# TinyISD1700_V2_2014-08-29sop.net
KiCad netlist of a schematic drawn in EAGLE
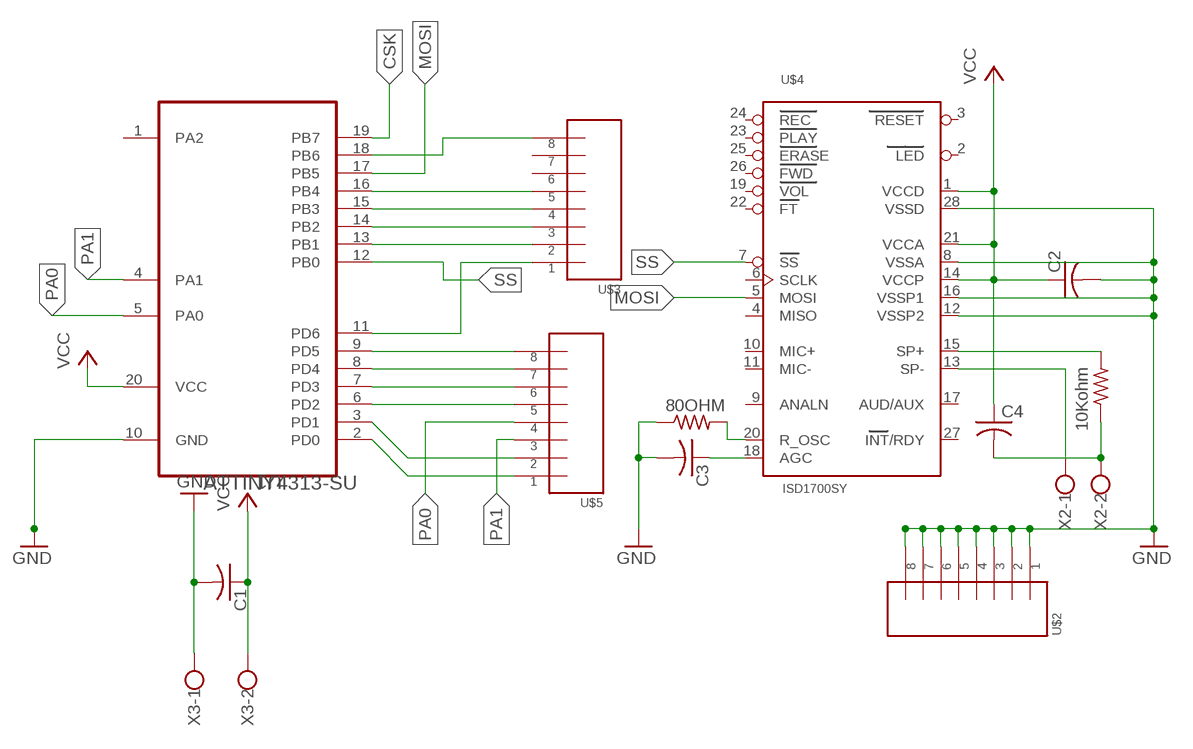
[diagram p0: schematic, sheet 1]

(export (version "E")
  (design (tool "Eeschema 10.0.6"))
  (components
    (comp (ref "80OHM")
      (value "R-US_0204/2V")
      (footprint "eagle-import:0204V")
      (libsource (lib "eagle-import") (part "R-US_0204/2V"))
    )
    (comp (ref "80OHM1")
      (value "10Kohm")
      (footprint "eagle-import:0204V")
      (libsource (lib "eagle-import") (part "R-US_0204/2V"))
    )
    (comp (ref "C1")
      (value "C-US050-030X075")
      (footprint "eagle-import:C050-030X075")
      (libsource (lib "eagle-import") (part "C-US050-030X075"))
    )
    (comp (ref "C2")
      (value "C-US050-030X075")
      (footprint "eagle-import:C050-030X075")
      (libsource (lib "eagle-import") (part "C-US050-030X075"))
    )
    (comp (ref "C3")
      (value "C-US050-030X075")
      (footprint "eagle-import:C050-030X075")
      (libsource (lib "eagle-import") (part "C-US050-030X075"))
    )
    (comp (ref "C4")
      (value "C-US050-030X075")
      (footprint "eagle-import:C050-030X075")
      (libsource (lib "eagle-import") (part "C-US050-030X075"))
    )
    (comp (ref "U$2")
      (value "8PIN_HEADER")
      (footprint "eagle-import:8PIN_HEADER")
      (fields (field (name "MF") "RENESAS") (field (name "MPN") "YSDKS128E10"))
      (libsource (lib "eagle-import") (part "8PIN_HEADER"))
    )
    (comp (ref "U$3")
      (value "8PIN_HEADER")
      (footprint "eagle-import:8PIN_HEADER")
      (fields (field (name "MF") "RENESAS") (field (name "MPN") "YSDKS128E10"))
      (libsource (lib "eagle-import") (part "8PIN_HEADER"))
    )
    (comp (ref "U$4")
      (value "ISD1700SY")
      (footprint "eagle-import:SO28W")
      (libsource (lib "eagle-import") (part "ISD1700SY"))
    )
    (comp (ref "U$5")
      (value "8PIN_HEADER")
      (footprint "eagle-import:8PIN_HEADER")
      (fields (field (name "MF") "RENESAS") (field (name "MPN") "YSDKS128E10"))
      (libsource (lib "eagle-import") (part "8PIN_HEADER"))
    )
    (comp (ref "U1")
      (value "ATTINY4313-SU")
      (footprint "eagle-import:SOIC127P1032X265-20N")
      (fields (field (name "MF") "MICROCHIP"))
      (libsource (lib "eagle-import") (part "ATTINY4313-SU"))
    )
    (comp (ref "X2")
      (value "W237-102")
      (footprint "eagle-import:W237-102")
      (fields (field (name "MPN") "237-102"))
      (libsource (lib "eagle-import") (part "W237-102"))
    )
    (comp (ref "X3")
      (value "W237-102")
      (footprint "eagle-import:W237-102")
      (fields (field (name "MPN") "237-102") (field (name "OC_NEWARK") "70K9898"))
      (libsource (lib "eagle-import") (part "W237-102"))
    )
  )
  (nets
    (net (code "1") (name "CSK") (class "Default")
      (node (ref "U1") (pin "19") (pinfunction "PB7_19") (pintype "bidirectional"))
    )
    (net (code "2") (name "GND") (class "Default")
      (node (ref "80OHM") (pin "1") (pinfunction "1_1") (pintype "passive"))
      (node (ref "C1") (pin "2") (pinfunction "2_2") (pintype "passive"))
      (node (ref "C2") (pin "2") (pinfunction "2_2") (pintype "passive"))
      (node (ref "C3") (pin "2") (pinfunction "2_2") (pintype "passive"))
      (node (ref "U$2") (pin "P$1") (pinfunction "P$1_P$1") (pintype "bidirectional"))
      (node (ref "U$2") (pin "P$2") (pinfunction "P$2_P$2") (pintype "bidirectional"))
      (node (ref "U$2") (pin "P$3") (pinfunction "P$3_P$3") (pintype "bidirectional"))
      (node (ref "U$2") (pin "P$4") (pinfunction "P$4_P$4") (pintype "bidirectional"))
      (node (ref "U$2") (pin "P$5") (pinfunction "P$5_P$5") (pintype "bidirectional"))
      (node (ref "U$2") (pin "P$6") (pinfunction "P$6_P$6") (pintype "bidirectional"))
      (node (ref "U$2") (pin "P$7") (pinfunction "P$7_P$7") (pintype "bidirectional"))
      (node (ref "U$2") (pin "P$8") (pinfunction "P$8_P$8") (pintype "bidirectional"))
      (node (ref "U$4") (pin "12") (pinfunction "VSSP2_12") (pintype "power_in"))
      (node (ref "U$4") (pin "16") (pinfunction "VSSP1_16") (pintype "power_in"))
      (node (ref "U$4") (pin "28") (pinfunction "VSSD_28") (pintype "power_in"))
      (node (ref "U$4") (pin "8") (pinfunction "VSSA_8") (pintype "power_in"))
      (node (ref "U1") (pin "10") (pinfunction "GND_10") (pintype "passive"))
      (node (ref "X3") (pin "1") (pinfunction "KL_1") (pintype "passive"))
    )
    (net (code "3") (name "MOSI") (class "Default")
      (node (ref "U$4") (pin "5") (pinfunction "MOSI_5") (pintype "input"))
      (node (ref "U1") (pin "17") (pinfunction "PB5_17") (pintype "bidirectional"))
    )
    (net (code "4") (name "Net-(U$4-AGC)") (class "Default")
      (node (ref "C3") (pin "1") (pinfunction "1_1") (pintype "passive"))
      (node (ref "U$4") (pin "18") (pinfunction "AGC_18") (pintype "passive"))
    )
    (net (code "5") (name "Net-(U$4-R_OSC)") (class "Default")
      (node (ref "80OHM") (pin "2") (pinfunction "2_2") (pintype "passive"))
      (node (ref "U$4") (pin "20") (pinfunction "R_OSC_20") (pintype "passive"))
    )
    (net (code "6") (name "Net-(U$4-SP+)") (class "Default")
      (node (ref "80OHM1") (pin "2") (pinfunction "2_2") (pintype "passive"))
      (node (ref "U$4") (pin "15") (pinfunction "SP+_15") (pintype "output"))
    )
    (net (code "7") (name "Net-(U$4-SP-)") (class "Default")
      (node (ref "U$4") (pin "13") (pinfunction "SP-_13") (pintype "output"))
      (node (ref "X2") (pin "1") (pinfunction "KL_1") (pintype "passive"))
    )
    (net (code "8") (name "Net-(U1-PB1)") (class "Default")
      (node (ref "U$3") (pin "P$2") (pinfunction "P$2_P$2") (pintype "bidirectional"))
      (node (ref "U1") (pin "13") (pinfunction "PB1_13") (pintype "bidirectional"))
    )
    (net (code "9") (name "Net-(U1-PB2)") (class "Default")
      (node (ref "U$3") (pin "P$3") (pinfunction "P$3_P$3") (pintype "bidirectional"))
      (node (ref "U1") (pin "14") (pinfunction "PB2_14") (pintype "bidirectional"))
    )
    (net (code "10") (name "Net-(U1-PB3)") (class "Default")
      (node (ref "U$3") (pin "P$4") (pinfunction "P$4_P$4") (pintype "bidirectional"))
      (node (ref "U1") (pin "15") (pinfunction "PB3_15") (pintype "bidirectional"))
    )
    (net (code "11") (name "Net-(U1-PB4)") (class "Default")
      (node (ref "U$3") (pin "P$5") (pinfunction "P$5_P$5") (pintype "bidirectional"))
      (node (ref "U1") (pin "16") (pinfunction "PB4_16") (pintype "bidirectional"))
    )
    (net (code "12") (name "Net-(U1-PB6)") (class "Default")
      (node (ref "U$3") (pin "P$8") (pinfunction "P$8_P$8") (pintype "bidirectional"))
      (node (ref "U1") (pin "18") (pinfunction "PB6_18") (pintype "bidirectional"))
    )
    (net (code "13") (name "Net-(U1-PD0)") (class "Default")
      (node (ref "U$5") (pin "P$1") (pinfunction "P$1_P$1") (pintype "bidirectional"))
      (node (ref "U1") (pin "2") (pinfunction "PD0_2") (pintype "bidirectional"))
    )
    (net (code "14") (name "Net-(U1-PD1)") (class "Default")
      (node (ref "U$5") (pin "P$2") (pinfunction "P$2_P$2") (pintype "bidirectional"))
      (node (ref "U1") (pin "3") (pinfunction "PD1_3") (pintype "bidirectional"))
    )
    (net (code "15") (name "Net-(U1-PD2)") (class "Default")
      (node (ref "U$5") (pin "P$5") (pinfunction "P$5_P$5") (pintype "bidirectional"))
      (node (ref "U1") (pin "6") (pinfunction "PD2_6") (pintype "bidirectional"))
    )
    (net (code "16") (name "Net-(U1-PD3)") (class "Default")
      (node (ref "U$5") (pin "P$6") (pinfunction "P$6_P$6") (pintype "bidirectional"))
      (node (ref "U1") (pin "7") (pinfunction "PD3_7") (pintype "bidirectional"))
    )
    (net (code "17") (name "Net-(U1-PD4)") (class "Default")
      (node (ref "U$5") (pin "P$7") (pinfunction "P$7_P$7") (pintype "bidirectional"))
      (node (ref "U1") (pin "8") (pinfunction "PD4_8") (pintype "bidirectional"))
    )
    (net (code "18") (name "Net-(U1-PD5)") (class "Default")
      (node (ref "U$5") (pin "P$8") (pinfunction "P$8_P$8") (pintype "bidirectional"))
      (node (ref "U1") (pin "9") (pinfunction "PD5_9") (pintype "bidirectional"))
    )
    (net (code "19") (name "Net-(U1-PD6)") (class "Default")
      (node (ref "U$3") (pin "P$1") (pinfunction "P$1_P$1") (pintype "bidirectional"))
      (node (ref "U1") (pin "11") (pinfunction "PD6_11") (pintype "bidirectional"))
    )
    (net (code "20") (name "Net-(X2B-KL)") (class "Default")
      (node (ref "80OHM1") (pin "1") (pinfunction "1_1") (pintype "passive"))
      (node (ref "C4") (pin "2") (pinfunction "2_2") (pintype "passive"))
      (node (ref "X2") (pin "2") (pinfunction "KL_2") (pintype "passive"))
    )
    (net (code "21") (name "PA0") (class "Default")
      (node (ref "U$5") (pin "P$4") (pinfunction "P$4_P$4") (pintype "bidirectional"))
      (node (ref "U1") (pin "5") (pinfunction "PA0_5") (pintype "bidirectional"))
    )
    (net (code "22") (name "PA1") (class "Default")
      (node (ref "U$5") (pin "P$3") (pinfunction "P$3_P$3") (pintype "bidirectional"))
      (node (ref "U1") (pin "4") (pinfunction "PA1_4") (pintype "bidirectional"))
    )
    (net (code "23") (name "SS") (class "Default")
      (node (ref "U$4") (pin "7") (pinfunction "SS_7") (pintype "input"))
      (node (ref "U1") (pin "12") (pinfunction "PB0_12") (pintype "bidirectional"))
    )
    (net (code "24") (name "VCC") (class "Default")
      (node (ref "C1") (pin "1") (pinfunction "1_1") (pintype "passive"))
      (node (ref "C2") (pin "1") (pinfunction "1_1") (pintype "passive"))
      (node (ref "C4") (pin "1") (pinfunction "1_1") (pintype "passive"))
      (node (ref "U$4") (pin "1") (pinfunction "VCCD_1") (pintype "power_in"))
      (node (ref "U$4") (pin "14") (pinfunction "VCCP_14") (pintype "power_in"))
      (node (ref "U$4") (pin "21") (pinfunction "VCCA_21") (pintype "power_in"))
      (node (ref "U1") (pin "20") (pinfunction "VCC_20") (pintype "power_in"))
      (node (ref "X3") (pin "2") (pinfunction "KL_2") (pintype "passive"))
    )
    (net (code "25") (name "unconnected-(U$3-PadP$6)") (class "Default")
      (node (ref "U$3") (pin "P$6") (pinfunction "P$6_P$6") (pintype "bidirectional"))
    )
    (net (code "26") (name "unconnected-(U$3-PadP$7)") (class "Default")
      (node (ref "U$3") (pin "P$7") (pinfunction "P$7_P$7") (pintype "bidirectional"))
    )
    (net (code "27") (name "unconnected-(U$4-ANALN-Pad9)") (class "Default")
      (node (ref "U$4") (pin "9") (pinfunction "ANALN_9") (pintype "input"))
    )
    (net (code "28") (name "unconnected-(U$4-AUD{slash}AUX-Pad17)") (class "Default")
      (node (ref "U$4") (pin "17") (pinfunction "AUD/AUX_17") (pintype "output"))
    )
    (net (code "29") (name "unconnected-(U$4-ERASE-Pad25)") (class "Default")
      (node (ref "U$4") (pin "25") (pinfunction "ERASE_25") (pintype "input"))
    )
    (net (code "30") (name "unconnected-(U$4-FT-Pad22)") (class "Default")
      (node (ref "U$4") (pin "22") (pinfunction "FT_22") (pintype "input"))
    )
    (net (code "31") (name "unconnected-(U$4-FWD-Pad26)") (class "Default")
      (node (ref "U$4") (pin "26") (pinfunction "FWD_26") (pintype "input"))
    )
    (net (code "32") (name "unconnected-(U$4-INT{slash}RDY-Pad27)") (class "Default")
      (node (ref "U$4") (pin "27") (pinfunction "INT/RDY_27") (pintype "bidirectional"))
    )
    (net (code "33") (name "unconnected-(U$4-LED-Pad2)") (class "Default")
      (node (ref "U$4") (pin "2") (pinfunction "LED_2") (pintype "input"))
    )
    (net (code "34") (name "unconnected-(U$4-MIC+-Pad10)") (class "Default")
      (node (ref "U$4") (pin "10") (pinfunction "MIC+_10") (pintype "input"))
    )
    (net (code "35") (name "unconnected-(U$4-MIC--Pad11)") (class "Default")
      (node (ref "U$4") (pin "11") (pinfunction "MIC-_11") (pintype "input"))
    )
    (net (code "36") (name "unconnected-(U$4-MISO-Pad4)") (class "Default")
      (node (ref "U$4") (pin "4") (pinfunction "MISO_4") (pintype "input"))
    )
    (net (code "37") (name "unconnected-(U$4-PLAY-Pad23)") (class "Default")
      (node (ref "U$4") (pin "23") (pinfunction "PLAY_23") (pintype "input"))
    )
    (net (code "38") (name "unconnected-(U$4-REC-Pad24)") (class "Default")
      (node (ref "U$4") (pin "24") (pinfunction "REC_24") (pintype "input"))
    )
    (net (code "39") (name "unconnected-(U$4-RESET-Pad3)") (class "Default")
      (node (ref "U$4") (pin "3") (pinfunction "RESET_3") (pintype "input"))
    )
    (net (code "40") (name "unconnected-(U$4-SCLK-Pad6)") (class "Default")
      (node (ref "U$4") (pin "6") (pinfunction "SCLK_6") (pintype "input"))
    )
    (net (code "41") (name "unconnected-(U$4-VOL-Pad19)") (class "Default")
      (node (ref "U$4") (pin "19") (pinfunction "VOL_19") (pintype "input"))
    )
    (net (code "42") (name "unconnected-(U1-PA2-Pad1)") (class "Default")
      (node (ref "U1") (pin "1") (pinfunction "PA2_1") (pintype "bidirectional"))
    )
  )
)
